# Mainboard_User_LED2_Connector.net
KiCad netlist of a schematic drawn in Altium Designer
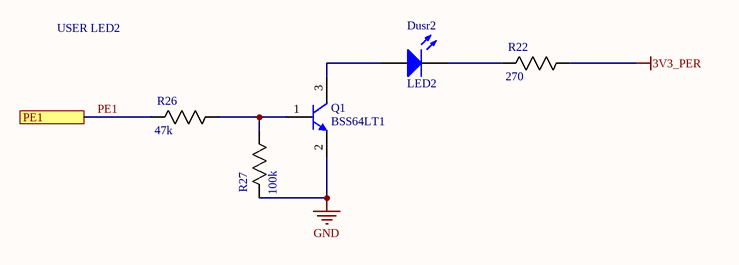
[diagram p0: Mainboard_User LED2 Connector.SchDoc]

(export (version "E")
  (design (tool "Eeschema 10.0.6"))
  (components
    (comp (ref "Dusr2")
      (value "LED2")
      (footprint "3.2X1.6X1.1")
      (description "Typical RED, GREEN, YELLOW, AMBER GaAs LED")
      (libsource (lib "AltiumLibraries") (part "LED GREEN SMD"))
    )
    (comp (ref "Q1")
      (value "BSS64LT1")
      (footprint "ONSC-SOT-23-3-318-08_V")
      (description "Driver Transistor, NPN Silicon, 3-Pin SOT-23, Tape and Reel")
      (fields (field (name "MANUFACTURER") "On Semiconductor"))
      (libsource (lib "Altium Content Vault") (part "ONSC-NPN-B1E2C3-3"))
    )
    (comp (ref "R22")
      (value "270")
      (footprint "0805")
      (description "RES SMD 270 OHM 5% 1/8W 0805")
      (fields (field (name "TOLERANCE") "5%"))
      (libsource (lib "AltiumLibraries") (part "RES 270.0 1/8W"))
    )
    (comp (ref "R26")
      (value "47k")
      (footprint "0805")
      (description "RES SMD 47K OHM 1% 1/8W 0805")
      (fields (field (name "TOLERANCE") "1%"))
      (libsource (lib "AltiumLibraries") (part "RES 47k 1/8W - 1%"))
    )
    (comp (ref "R27")
      (value "100k")
      (footprint "0805")
      (description "RES SMD 100K OHM 1% 1/8W 0805")
      (fields (field (name "TOLERANCE") "1%"))
      (libsource (lib "AltiumLibraries") (part "RES 100k 1/8W - 1%"))
    )
  )
  (nets
    (net (code "1") (name "/PE1") (class "Default")
      (node (ref "R26") (pin "2") (pinfunction "R2_2") (pintype "passive"))
    )
    (net (code "2") (name "3V3_PER") (class "Default")
      (node (ref "R22") (pin "1") (pinfunction "R1_1") (pintype "passive"))
    )
    (net (code "3") (name "GND") (class "Default")
      (node (ref "Q1") (pin "2") (pinfunction "E_2") (pintype "passive"))
      (node (ref "R27") (pin "2") (pinfunction "R2_2") (pintype "passive"))
    )
    (net (code "4") (name "Net-(Dusr2-A)") (class "Default")
      (node (ref "Dusr2") (pin "1") (pinfunction "A_1") (pintype "passive"))
      (node (ref "Q1") (pin "3") (pinfunction "C_3") (pintype "passive"))
    )
    (net (code "5") (name "Net-(Dusr2-K)") (class "Default")
      (node (ref "Dusr2") (pin "2") (pinfunction "K_2") (pintype "passive"))
      (node (ref "R22") (pin "2") (pinfunction "R2_2") (pintype "passive"))
    )
    (net (code "6") (name "Net-(Q1-B)") (class "Default")
      (node (ref "Q1") (pin "1") (pinfunction "B_1") (pintype "passive"))
      (node (ref "R26") (pin "1") (pinfunction "R1_1") (pintype "passive"))
      (node (ref "R27") (pin "1") (pinfunction "R1_1") (pintype "passive"))
    )
  )
)
